# SCH_Flight-Computer-V4_2024-07-20.net
KiCad netlist of a schematic drawn in EasyEDA
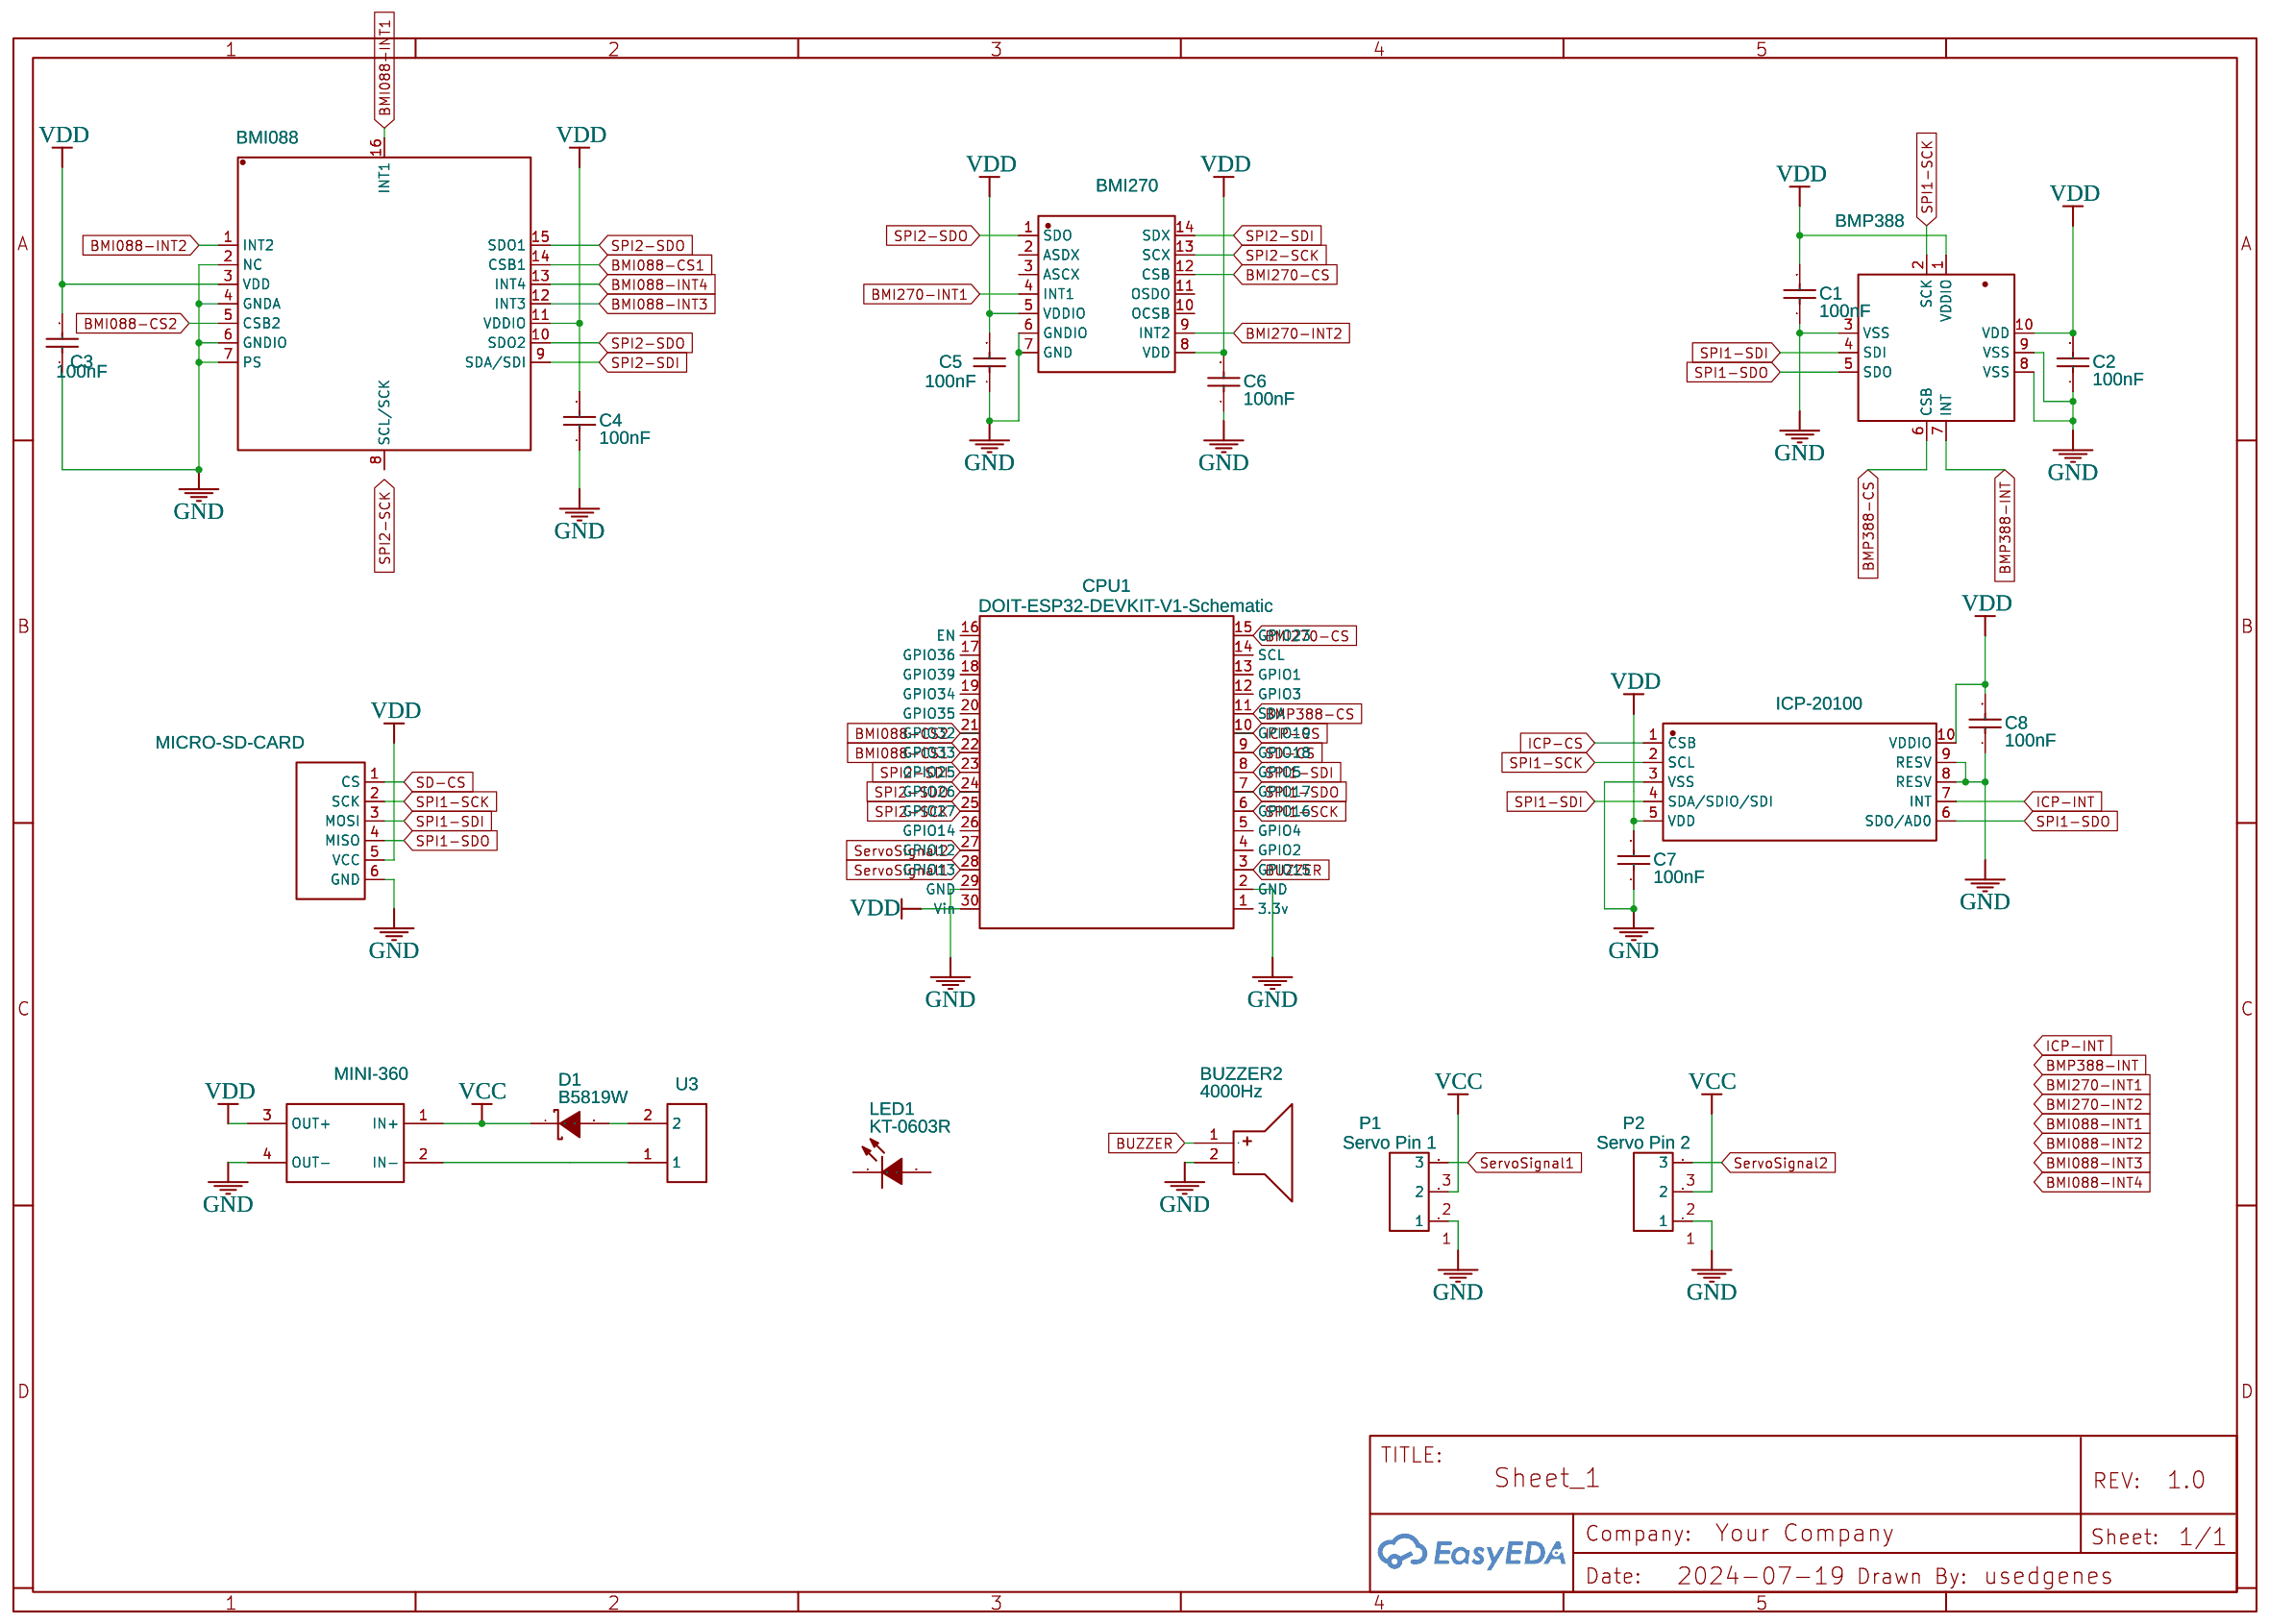
[diagram p0: schematic sheet]

(export (version "E")
  (design (tool "Eeschema 10.0.6"))
  (components
    (comp (ref "BMI088")
      (value "BMI088")
      (fields (field (name "Manufacturer") "Bosch(博世)"))
      (libsource (lib "") (part "BMI088"))
    )
    (comp (ref "BMI270")
      (value "BMI270")
      (fields (field (name "Manufacturer") "Bosch(博世)"))
      (libsource (lib "") (part "BMI270"))
    )
    (comp (ref "BMP388")
      (value "BMP388")
      (fields (field (name "Manufacturer") "Bosch(博世)"))
      (libsource (lib "") (part "BMP388"))
    )
    (comp (ref "BUZZER2")
      (value "4000Hz")
      (fields
        (field (name "Manufacturer Part") "SKY-1475-0540-45P7.6")
        (field (name "Manufacturer") "S&S(海旭)")
      )
      (libsource (lib "") (part "SKY-1475-0540-45P7.6"))
    )
    (comp (ref "C1")
      (value "100nF")
      (fields
        (field (name "Manufacturer Part") "CL05B104KO5NNNC")
        (field (name "Manufacturer") "SAMSUNG(三星)")
      )
      (libsource (lib "") (part "CL05B104KO5NNNC"))
    )
    (comp (ref "C2")
      (value "100nF")
      (fields
        (field (name "Manufacturer Part") "CL05B104KO5NNNC")
        (field (name "Manufacturer") "SAMSUNG(三星)")
      )
      (libsource (lib "") (part "CL05B104KO5NNNC"))
    )
    (comp (ref "C3")
      (value "100nF")
      (fields
        (field (name "Manufacturer Part") "CL05B104KO5NNNC")
        (field (name "Manufacturer") "SAMSUNG(三星)")
      )
      (libsource (lib "") (part "CL05B104KO5NNNC"))
    )
    (comp (ref "C4")
      (value "100nF")
      (fields
        (field (name "Manufacturer Part") "CL05B104KO5NNNC")
        (field (name "Manufacturer") "SAMSUNG(三星)")
      )
      (libsource (lib "") (part "CL05B104KO5NNNC"))
    )
    (comp (ref "C5")
      (value "100nF")
      (fields
        (field (name "Manufacturer Part") "CL05B104KO5NNNC")
        (field (name "Manufacturer") "SAMSUNG(三星)")
      )
      (libsource (lib "") (part "CL05B104KO5NNNC"))
    )
    (comp (ref "C6")
      (value "100nF")
      (fields
        (field (name "Manufacturer Part") "CL05B104KO5NNNC")
        (field (name "Manufacturer") "SAMSUNG(三星)")
      )
      (libsource (lib "") (part "CL05B104KO5NNNC"))
    )
    (comp (ref "C7")
      (value "100nF")
      (fields
        (field (name "Manufacturer Part") "CL05B104KO5NNNC")
        (field (name "Manufacturer") "SAMSUNG(三星)")
      )
      (libsource (lib "") (part "CL05B104KO5NNNC"))
    )
    (comp (ref "C8")
      (value "100nF")
      (fields
        (field (name "Manufacturer Part") "CL05B104KO5NNNC")
        (field (name "Manufacturer") "SAMSUNG(三星)")
      )
      (libsource (lib "") (part "CL05B104KO5NNNC"))
    )
    (comp (ref "CPU1")
      (value "DOIT-ESP32-DEVKIT-V1-Schematic")
      (fields (field (name "Manufacturer Part") "NONE"))
      (libsource (lib "") (part "DOIT-ESP32-DEVKIT-V1-Schematic"))
    )
    (comp (ref "D1")
      (value "B5819W")
      (fields (field (name "Manufacturer") "MDD(辰达半导体)"))
      (libsource (lib "") (part "B5819W"))
    )
    (comp (ref "ICP-20100")
      (value "ICP-20100")
      (fields (field (name "Manufacturer") "TDK"))
      (libsource (lib "") (part "ICP-20100"))
    )
    (comp (ref "LED1")
      (value "KT-0603R")
      (fields (field (name "Manufacturer") "KENTO"))
      (libsource (lib "") (part "KT-0603R"))
    )
    (comp (ref "MICRO-SD-CARD") (value "MicroSDCardAdapter") (libsource (lib "") (part "MicroSDCardAdapter")))
    (comp (ref "MINI-360") (value "MINI-360") (libsource (lib "") (part "MINI-360")))
    (comp (ref "P1")
      (value "Servo Pin 1")
      (fields
        (field (name "Manufacturer Part") "Female headerHDR1X8-2.54")
        (field (name "Manufacturer") "BOOMELE")
      )
      (libsource (lib "") (part "HEADER PAD 3X RMM COPY"))
    )
    (comp (ref "P2")
      (value "Servo Pin 2")
      (fields
        (field (name "Manufacturer Part") "Female headerHDR1X8-2.54")
        (field (name "Manufacturer") "BOOMELE")
      )
      (libsource (lib "") (part "HEADER PAD 3X RMM COPY"))
    )
    (comp (ref "U3") (value "Power Pins") (libsource (lib "") (part "1X2")))
  )
  (nets
    (net (code "1") (name "BMI088-CS1") (class "Default")
      (node (ref "BMI088") (pin "14") (pinfunction "CSB1_14") (pintype "unspecified"))
      (node (ref "CPU1") (pin "22") (pinfunction "GPIO33_22") (pintype "unspecified"))
    )
    (net (code "2") (name "BMI088-CS2") (class "Default")
      (node (ref "BMI088") (pin "5") (pinfunction "CSB2_5") (pintype "unspecified"))
      (node (ref "CPU1") (pin "21") (pinfunction "GPIO32_21") (pintype "unspecified"))
    )
    (net (code "3") (name "BMI088-INT1") (class "Default")
      (node (ref "BMI088") (pin "16") (pinfunction "INT1_16") (pintype "unspecified"))
    )
    (net (code "4") (name "BMI088-INT2") (class "Default")
      (node (ref "BMI088") (pin "1") (pinfunction "INT2_1") (pintype "unspecified"))
    )
    (net (code "5") (name "BMI088-INT3") (class "Default")
      (node (ref "BMI088") (pin "12") (pinfunction "INT3_12") (pintype "unspecified"))
    )
    (net (code "6") (name "BMI088-INT4") (class "Default")
      (node (ref "BMI088") (pin "13") (pinfunction "INT4_13") (pintype "unspecified"))
    )
    (net (code "7") (name "BMI270-CS") (class "Default")
      (node (ref "BMI270") (pin "12") (pinfunction "CSB_12") (pintype "unspecified"))
      (node (ref "CPU1") (pin "15") (pinfunction "GPIO23_15") (pintype "unspecified"))
    )
    (net (code "8") (name "BMI270-INT1") (class "Default")
      (node (ref "BMI270") (pin "4") (pinfunction "INT1_4") (pintype "unspecified"))
    )
    (net (code "9") (name "BMI270-INT2") (class "Default")
      (node (ref "BMI270") (pin "9") (pinfunction "INT2_9") (pintype "unspecified"))
    )
    (net (code "10") (name "BMP388-CS") (class "Default")
      (node (ref "BMP388") (pin "6") (pinfunction "CSB_6") (pintype "unspecified"))
      (node (ref "CPU1") (pin "11") (pinfunction "SDA_11") (pintype "unspecified"))
    )
    (net (code "11") (name "BMP388-INT") (class "Default")
      (node (ref "BMP388") (pin "7") (pinfunction "INT_7") (pintype "unspecified"))
    )
    (net (code "12") (name "BUZZER") (class "Default")
      (node (ref "BUZZER2") (pin "1") (pinfunction "+_1") (pintype "unspecified"))
      (node (ref "CPU1") (pin "3") (pinfunction "GPIO15_3") (pintype "unspecified"))
    )
    (net (code "13") (name "GND") (class "Default")
      (node (ref "BMI088") (pin "2") (pinfunction "NC_2") (pintype "unspecified"))
      (node (ref "BMI088") (pin "4") (pinfunction "GNDA_4") (pintype "unspecified"))
      (node (ref "BMI088") (pin "6") (pinfunction "GNDIO_6") (pintype "unspecified"))
      (node (ref "BMI088") (pin "7") (pinfunction "PS_7") (pintype "unspecified"))
      (node (ref "BMI270") (pin "6") (pinfunction "GNDIO_6") (pintype "unspecified"))
      (node (ref "BMI270") (pin "7") (pinfunction "GND_7") (pintype "unspecified"))
      (node (ref "BMP388") (pin "3") (pinfunction "VSS_3") (pintype "unspecified"))
      (node (ref "BMP388") (pin "8") (pinfunction "VSS_8") (pintype "unspecified"))
      (node (ref "BMP388") (pin "9") (pinfunction "VSS_9") (pintype "unspecified"))
      (node (ref "BUZZER2") (pin "2") (pinfunction "-_2") (pintype "unspecified"))
      (node (ref "C1") (pin "1") (pinfunction "1_1") (pintype "input"))
      (node (ref "C2") (pin "1") (pinfunction "1_1") (pintype "input"))
      (node (ref "C3") (pin "1") (pinfunction "1_1") (pintype "input"))
      (node (ref "C4") (pin "1") (pinfunction "1_1") (pintype "input"))
      (node (ref "C5") (pin "1") (pinfunction "1_1") (pintype "input"))
      (node (ref "C6") (pin "1") (pinfunction "1_1") (pintype "input"))
      (node (ref "C7") (pin "1") (pinfunction "1_1") (pintype "input"))
      (node (ref "C8") (pin "1") (pinfunction "1_1") (pintype "input"))
      (node (ref "CPU1") (pin "2") (pinfunction "GND_2") (pintype "unspecified"))
      (node (ref "CPU1") (pin "29") (pinfunction "GND_29") (pintype "unspecified"))
      (node (ref "ICP-20100") (pin "3") (pinfunction "VSS_3") (pintype "unspecified"))
      (node (ref "ICP-20100") (pin "8") (pinfunction "RESV_8") (pintype "unspecified"))
      (node (ref "ICP-20100") (pin "9") (pinfunction "RESV_9") (pintype "unspecified"))
      (node (ref "MICRO-SD-CARD") (pin "6") (pinfunction "GND_6") (pintype "passive"))
      (node (ref "MINI-360") (pin "4") (pinfunction "OUT-_4") (pintype "unspecified"))
      (node (ref "P1") (pin "1") (pinfunction "1_1") (pintype "unspecified"))
      (node (ref "P2") (pin "1") (pinfunction "1_1") (pintype "unspecified"))
    )
    (net (code "14") (name "ICP-CS") (class "Default")
      (node (ref "CPU1") (pin "10") (pinfunction "GPIO19_10") (pintype "unspecified"))
      (node (ref "ICP-20100") (pin "1") (pinfunction "CSB_1") (pintype "unspecified"))
    )
    (net (code "15") (name "ICP-INT") (class "Default")
      (node (ref "ICP-20100") (pin "7") (pinfunction "INT_7") (pintype "unspecified"))
    )
    (net (code "16") (name "Net-(D1-A)") (class "Default")
      (node (ref "D1") (pin "2") (pinfunction "A_2") (pintype "unspecified"))
      (node (ref "U3") (pin "2") (pinfunction "2_2") (pintype "unspecified"))
    )
    (net (code "17") (name "Net-(MINI-360-IN-)") (class "Default")
      (node (ref "MINI-360") (pin "2") (pinfunction "IN-_2") (pintype "unspecified"))
      (node (ref "U3") (pin "1") (pinfunction "1_1") (pintype "unspecified"))
    )
    (net (code "18") (name "SD-CS") (class "Default")
      (node (ref "CPU1") (pin "9") (pinfunction "GPIO18_9") (pintype "unspecified"))
      (node (ref "MICRO-SD-CARD") (pin "1") (pinfunction "CS_1") (pintype "bidirectional"))
    )
    (net (code "19") (name "SPI1-SCK") (class "Default")
      (node (ref "BMP388") (pin "2") (pinfunction "SCK_2") (pintype "unspecified"))
      (node (ref "CPU1") (pin "6") (pinfunction "GPIO16_6") (pintype "unspecified"))
      (node (ref "ICP-20100") (pin "2") (pinfunction "SCL_2") (pintype "unspecified"))
      (node (ref "MICRO-SD-CARD") (pin "2") (pinfunction "SCK_2") (pintype "bidirectional"))
    )
    (net (code "20") (name "SPI1-SDI") (class "Default")
      (node (ref "BMP388") (pin "4") (pinfunction "SDI_4") (pintype "unspecified"))
      (node (ref "CPU1") (pin "8") (pinfunction "GPIO5_8") (pintype "unspecified"))
      (node (ref "ICP-20100") (pin "4") (pinfunction "SDA/SDIO/SDI_4") (pintype "unspecified"))
      (node (ref "MICRO-SD-CARD") (pin "3") (pinfunction "MOSI_3") (pintype "passive"))
    )
    (net (code "21") (name "SPI1-SDO") (class "Default")
      (node (ref "BMP388") (pin "5") (pinfunction "SDO_5") (pintype "unspecified"))
      (node (ref "CPU1") (pin "7") (pinfunction "GPIO17_7") (pintype "unspecified"))
      (node (ref "ICP-20100") (pin "6") (pinfunction "SDO/AD0_6") (pintype "unspecified"))
      (node (ref "MICRO-SD-CARD") (pin "4") (pinfunction "MISO_4") (pintype "bidirectional"))
    )
    (net (code "22") (name "SPI2-SCK") (class "Default")
      (node (ref "BMI270") (pin "13") (pinfunction "SCX_13") (pintype "unspecified"))
      (node (ref "CPU1") (pin "25") (pinfunction "GPIO27_25") (pintype "unspecified"))
    )
    (net (code "23") (name "SPI2-SDI") (class "Default")
      (node (ref "BMI088") (pin "9") (pinfunction "SDA/SDI_9") (pintype "unspecified"))
      (node (ref "BMI270") (pin "14") (pinfunction "SDX_14") (pintype "unspecified"))
      (node (ref "CPU1") (pin "23") (pinfunction "GPIO25_23") (pintype "unspecified"))
    )
    (net (code "24") (name "SPI2-SDO") (class "Default")
      (node (ref "BMI088") (pin "10") (pinfunction "SDO2_10") (pintype "unspecified"))
      (node (ref "BMI088") (pin "15") (pinfunction "SDO1_15") (pintype "unspecified"))
      (node (ref "BMI270") (pin "1") (pinfunction "SDO_1") (pintype "unspecified"))
      (node (ref "CPU1") (pin "24") (pinfunction "GPIO26_24") (pintype "unspecified"))
    )
    (net (code "25") (name "ServoSignal1") (class "Default")
      (node (ref "CPU1") (pin "28") (pinfunction "GPIO13_28") (pintype "unspecified"))
      (node (ref "P1") (pin "3") (pinfunction "3_3") (pintype "unspecified"))
    )
    (net (code "26") (name "ServoSignal2") (class "Default")
      (node (ref "CPU1") (pin "27") (pinfunction "GPIO12_27") (pintype "unspecified"))
      (node (ref "P2") (pin "3") (pinfunction "3_3") (pintype "unspecified"))
    )
    (net (code "27") (name "VCC") (class "Default")
      (node (ref "D1") (pin "1") (pinfunction "K_1") (pintype "unspecified"))
      (node (ref "MINI-360") (pin "1") (pinfunction "IN+_1") (pintype "unspecified"))
      (node (ref "P1") (pin "2") (pinfunction "2_2") (pintype "unspecified"))
      (node (ref "P2") (pin "2") (pinfunction "2_2") (pintype "unspecified"))
    )
    (net (code "28") (name "VDD") (class "Default")
      (node (ref "BMI088") (pin "11") (pinfunction "VDDIO_11") (pintype "unspecified"))
      (node (ref "BMI088") (pin "3") (pinfunction "VDD_3") (pintype "unspecified"))
      (node (ref "BMI270") (pin "5") (pinfunction "VDDIO_5") (pintype "unspecified"))
      (node (ref "BMI270") (pin "8") (pinfunction "VDD_8") (pintype "unspecified"))
      (node (ref "BMP388") (pin "1") (pinfunction "VDDIO_1") (pintype "unspecified"))
      (node (ref "BMP388") (pin "10") (pinfunction "VDD_10") (pintype "unspecified"))
      (node (ref "C1") (pin "2") (pinfunction "2_2") (pintype "input"))
      (node (ref "C2") (pin "2") (pinfunction "2_2") (pintype "input"))
      (node (ref "C3") (pin "2") (pinfunction "2_2") (pintype "input"))
      (node (ref "C4") (pin "2") (pinfunction "2_2") (pintype "input"))
      (node (ref "C5") (pin "2") (pinfunction "2_2") (pintype "input"))
      (node (ref "C6") (pin "2") (pinfunction "2_2") (pintype "input"))
      (node (ref "C7") (pin "2") (pinfunction "2_2") (pintype "input"))
      (node (ref "C8") (pin "2") (pinfunction "2_2") (pintype "input"))
      (node (ref "CPU1") (pin "30") (pinfunction "Vin_30") (pintype "unspecified"))
      (node (ref "ICP-20100") (pin "10") (pinfunction "VDDIO_10") (pintype "unspecified"))
      (node (ref "ICP-20100") (pin "5") (pinfunction "VDD_5") (pintype "unspecified"))
      (node (ref "MICRO-SD-CARD") (pin "5") (pinfunction "VCC_5") (pintype "passive"))
      (node (ref "MINI-360") (pin "3") (pinfunction "OUT+_3") (pintype "unspecified"))
    )
    (net (code "29") (name "unconnected-(BMI088-SCL{slash}SCK-Pad8)") (class "Default")
      (node (ref "BMI088") (pin "8") (pinfunction "SCL/SCK_8") (pintype "unspecified"))
    )
    (net (code "30") (name "unconnected-(BMI270-ASCX-Pad3)") (class "Default")
      (node (ref "BMI270") (pin "3") (pinfunction "ASCX_3") (pintype "unspecified"))
    )
    (net (code "31") (name "unconnected-(BMI270-ASDX-Pad2)") (class "Default")
      (node (ref "BMI270") (pin "2") (pinfunction "ASDX_2") (pintype "unspecified"))
    )
    (net (code "32") (name "unconnected-(BMI270-OCSB-Pad10)") (class "Default")
      (node (ref "BMI270") (pin "10") (pinfunction "OCSB_10") (pintype "unspecified"))
    )
    (net (code "33") (name "unconnected-(BMI270-OSDO-Pad11)") (class "Default")
      (node (ref "BMI270") (pin "11") (pinfunction "OSDO_11") (pintype "unspecified"))
    )
    (net (code "34") (name "unconnected-(CPU1-3.3v-Pad1)") (class "Default")
      (node (ref "CPU1") (pin "1") (pinfunction "3.3v_1") (pintype "unspecified"))
    )
    (net (code "35") (name "unconnected-(CPU1-EN-Pad16)") (class "Default")
      (node (ref "CPU1") (pin "16") (pinfunction "EN_16") (pintype "unspecified"))
    )
    (net (code "36") (name "unconnected-(CPU1-GPIO1-Pad13)") (class "Default")
      (node (ref "CPU1") (pin "13") (pinfunction "GPIO1_13") (pintype "unspecified"))
    )
    (net (code "37") (name "unconnected-(CPU1-GPIO2-Pad4)") (class "Default")
      (node (ref "CPU1") (pin "4") (pinfunction "GPIO2_4") (pintype "unspecified"))
    )
    (net (code "38") (name "unconnected-(CPU1-GPIO3-Pad12)") (class "Default")
      (node (ref "CPU1") (pin "12") (pinfunction "GPIO3_12") (pintype "unspecified"))
    )
    (net (code "39") (name "unconnected-(CPU1-GPIO4-Pad5)") (class "Default")
      (node (ref "CPU1") (pin "5") (pinfunction "GPIO4_5") (pintype "unspecified"))
    )
    (net (code "40") (name "unconnected-(CPU1-GPIO14-Pad26)") (class "Default")
      (node (ref "CPU1") (pin "26") (pinfunction "GPIO14_26") (pintype "unspecified"))
    )
    (net (code "41") (name "unconnected-(CPU1-GPIO34-Pad19)") (class "Default")
      (node (ref "CPU1") (pin "19") (pinfunction "GPIO34_19") (pintype "unspecified"))
    )
    (net (code "42") (name "unconnected-(CPU1-GPIO35-Pad20)") (class "Default")
      (node (ref "CPU1") (pin "20") (pinfunction "GPIO35_20") (pintype "unspecified"))
    )
    (net (code "43") (name "unconnected-(CPU1-GPIO36-Pad17)") (class "Default")
      (node (ref "CPU1") (pin "17") (pinfunction "GPIO36_17") (pintype "unspecified"))
    )
    (net (code "44") (name "unconnected-(CPU1-GPIO39-Pad18)") (class "Default")
      (node (ref "CPU1") (pin "18") (pinfunction "GPIO39_18") (pintype "unspecified"))
    )
    (net (code "45") (name "unconnected-(CPU1-SCL-Pad14)") (class "Default")
      (node (ref "CPU1") (pin "14") (pinfunction "SCL_14") (pintype "unspecified"))
    )
    (net (code "46") (name "unconnected-(LED1-A-Pad2)") (class "Default")
      (node (ref "LED1") (pin "2") (pinfunction "A_2") (pintype "unspecified"))
    )
    (net (code "47") (name "unconnected-(LED1-K-Pad1)") (class "Default")
      (node (ref "LED1") (pin "1") (pinfunction "K_1") (pintype "unspecified"))
    )
  )
)
